# uARM.net
KiCad netlist of a schematic drawn in Altium Designer
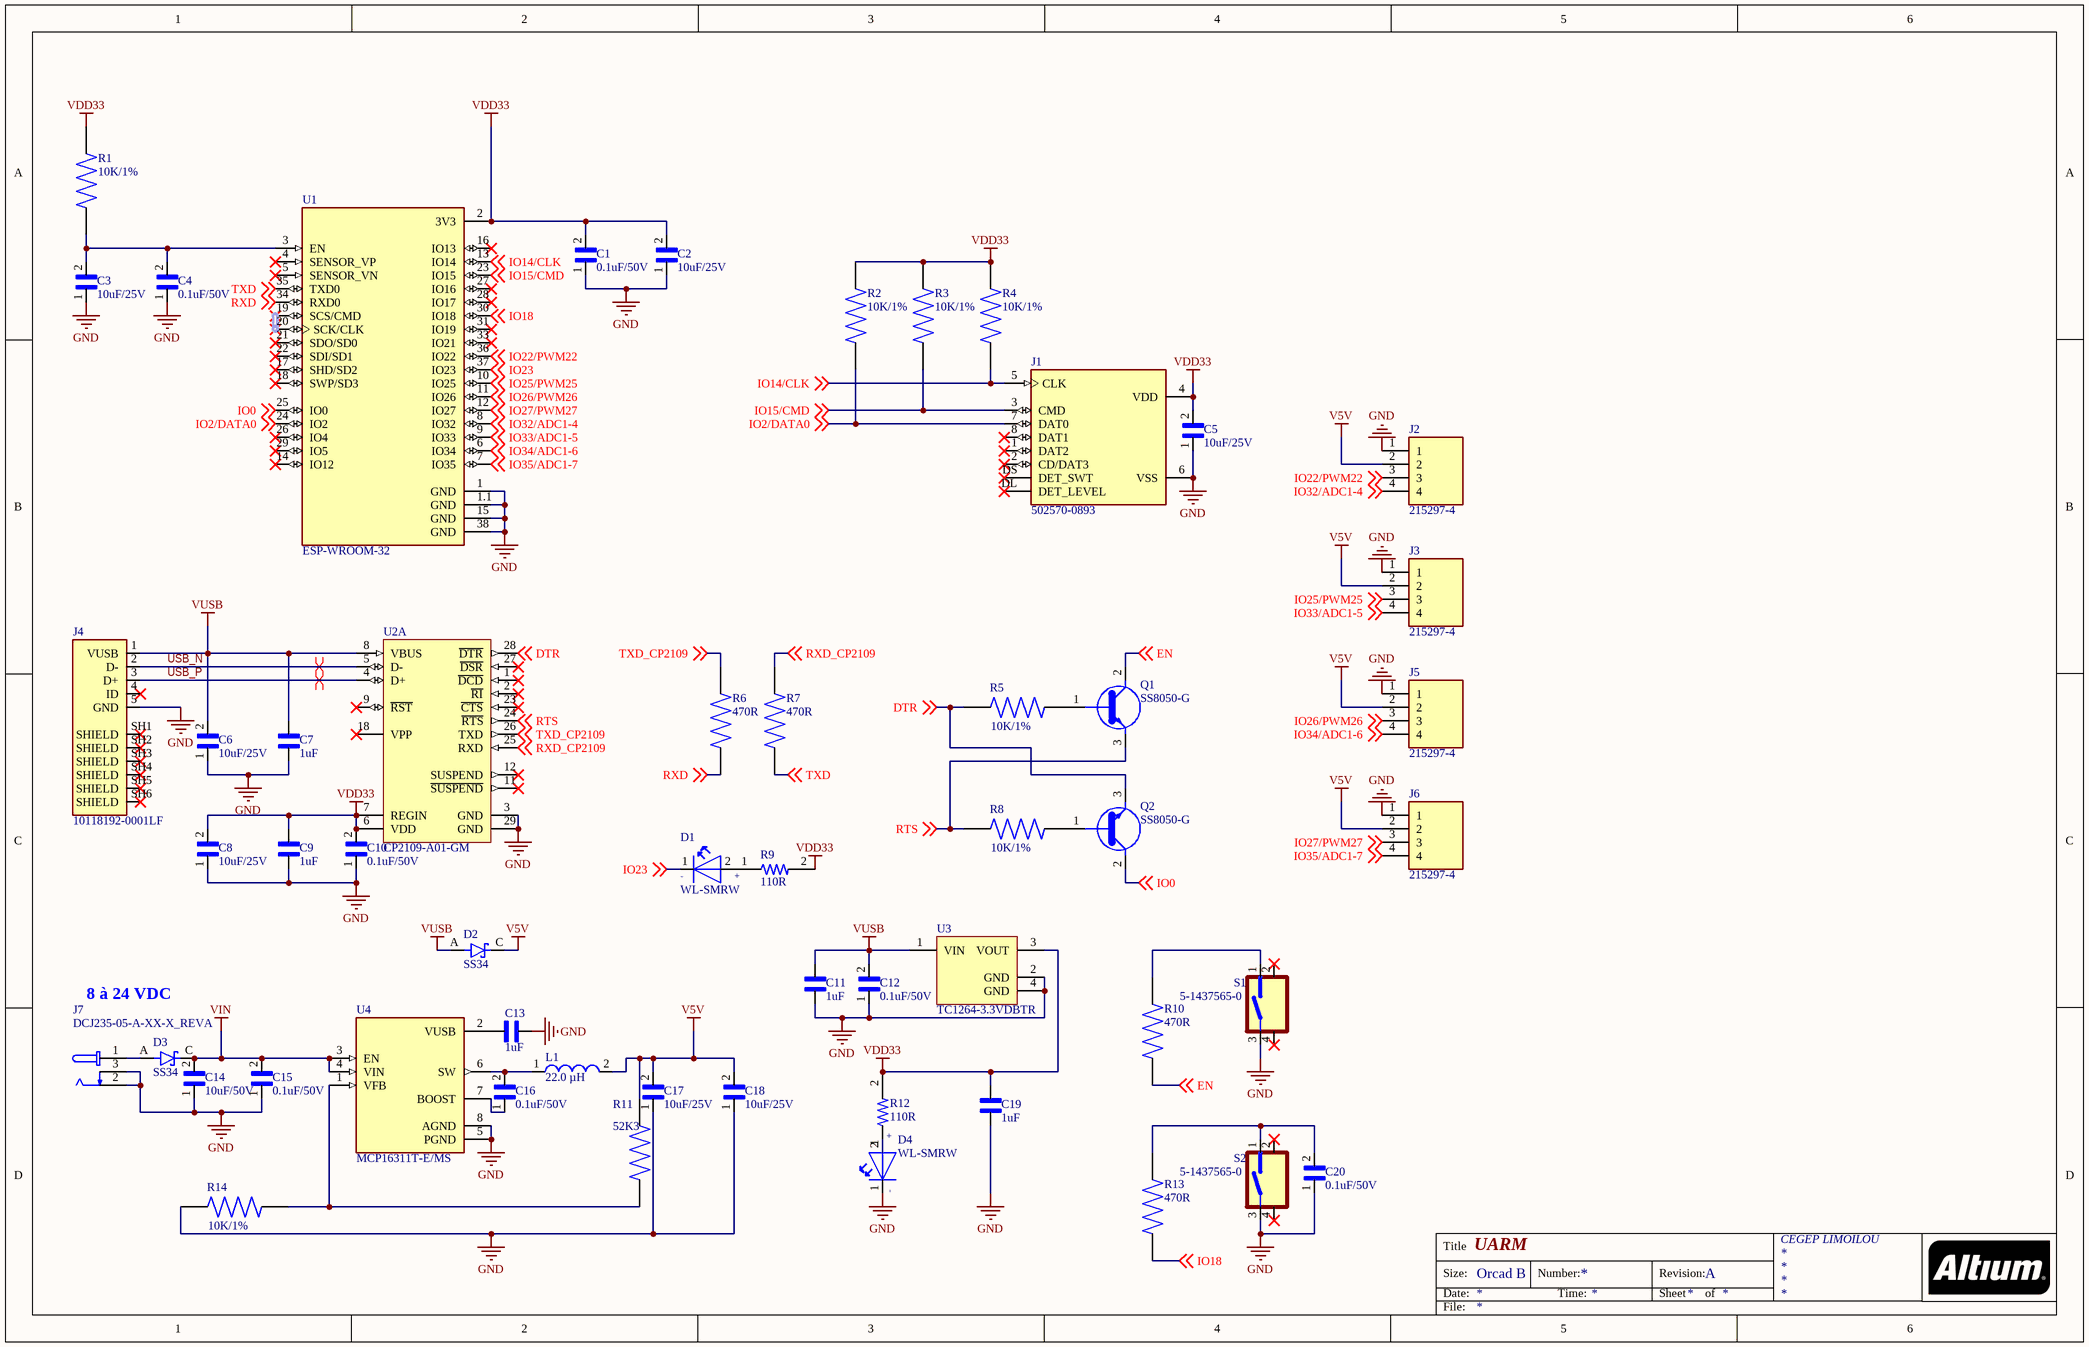
[diagram p0: uARM.SchDoc]

(export (version "E")
  (design (tool "Eeschema 10.0.6"))
  (components
    (comp (ref "C1")
      (value "0.1uF/50V")
      (footprint "08055C104KAT4A:CAPC2012X94N")
      (description ".1UF 50V 10% 0805")
      (fields (field (name "MF") "{'manufacturer': u'AVX'}") (field (name "MP") "08055C104KAT4A"))
      (libsource (lib "*") (part "08055C104KAT4A"))
    )
    (comp (ref "C2")
      (value "10uF/25V")
      (footprint "CL21A106KAYNNNE:CAPC2012X135N")
      (description "Cap Ceramic 10uF 25V X5R 10% SMD 0805 85Â°C Embossed T/R")
      (fields (field (name "MP") "CL21A106KAYNNNE") (field (name "MF") "{'manufacturer': u'Samsung'}"))
      (libsource (lib "*") (part "CL21A106KAYNNNE"))
    )
    (comp (ref "C3")
      (value "10uF/25V")
      (footprint "CL21A106KAYNNNE:CAPC2012X135N")
      (description "Cap Ceramic 10uF 25V X5R 10% SMD 0805 85Â°C Embossed T/R")
      (fields (field (name "MP") "CL21A106KAYNNNE") (field (name "MF") "{'manufacturer': u'Samsung'}"))
      (libsource (lib "*") (part "CL21A106KAYNNNE"))
    )
    (comp (ref "C4")
      (value "0.1uF/50V")
      (footprint "08055C104KAT4A:CAPC2012X94N")
      (description ".1UF 50V 10% 0805")
      (fields (field (name "MF") "{'manufacturer': u'AVX'}") (field (name "MP") "08055C104KAT4A"))
      (libsource (lib "*") (part "08055C104KAT4A"))
    )
    (comp (ref "C5")
      (value "10uF/25V")
      (footprint "CL21A106KAYNNNE:CAPC2012X135N")
      (description "Cap Ceramic 10uF 25V X5R 10% SMD 0805 85Â°C Embossed T/R")
      (fields (field (name "MP") "CL21A106KAYNNNE") (field (name "MF") "{'manufacturer': u'Samsung'}"))
      (libsource (lib "*") (part "CL21A106KAYNNNE"))
    )
    (comp (ref "C6")
      (value "10uF/25V")
      (footprint "CL21A106KAYNNNE:CAPC2012X135N")
      (description "Cap Ceramic 10uF 25V X5R 10% SMD 0805 85Â°C Embossed T/R")
      (fields (field (name "MP") "CL21A106KAYNNNE") (field (name "MF") "{'manufacturer': u'Samsung'}"))
      (libsource (lib "*") (part "CL21A106KAYNNNE"))
    )
    (comp (ref "C7")
      (value "1uF")
      (footprint "885012207022:WCAP-CSGP_885012207022")
      (fields
        (field (name "MF") "{'manufacturer': u'Wurth Electronics Inc'}")
        (field (name "MP") "885012207022")
      )
      (libsource (lib "") (part "885012207022_1"))
    )
    (comp (ref "C8")
      (value "10uF/25V")
      (footprint "CL21A106KAYNNNE:CAPC2012X135N")
      (description "Cap Ceramic 10uF 25V X5R 10% SMD 0805 85Â°C Embossed T/R")
      (fields (field (name "MP") "CL21A106KAYNNNE") (field (name "MF") "{'manufacturer': u'Samsung'}"))
      (libsource (lib "*") (part "CL21A106KAYNNNE"))
    )
    (comp (ref "C9")
      (value "1uF")
      (footprint "885012207022:WCAP-CSGP_885012207022")
      (fields
        (field (name "MF") "{'manufacturer': u'Wurth Electronics Inc'}")
        (field (name "MP") "885012207022")
      )
      (libsource (lib "") (part "885012207022_1"))
    )
    (comp (ref "C10")
      (value "0.1uF/50V")
      (footprint "08055C104KAT4A:CAPC2012X94N")
      (description ".1UF 50V 10% 0805")
      (fields (field (name "MF") "{'manufacturer': u'AVX'}") (field (name "MP") "08055C104KAT4A"))
      (libsource (lib "*") (part "08055C104KAT4A"))
    )
    (comp (ref "C11")
      (value "1uF")
      (footprint "885012207022:WCAP-CSGP_885012207022")
      (fields
        (field (name "MF") "{'manufacturer': u'Wurth Electronics Inc'}")
        (field (name "MP") "885012207022")
      )
      (libsource (lib "") (part "885012207022_1"))
    )
    (comp (ref "C12")
      (value "0.1uF/50V")
      (footprint "08055C104KAT4A:CAPC2012X94N")
      (description ".1UF 50V 10% 0805")
      (fields (field (name "MF") "{'manufacturer': u'AVX'}") (field (name "MP") "08055C104KAT4A"))
      (libsource (lib "*") (part "08055C104KAT4A"))
    )
    (comp (ref "C13")
      (value "1uF")
      (footprint "885012207022:WCAP-CSGP_885012207022")
      (fields
        (field (name "MF") "{'manufacturer': u'Wurth Electronics Inc'}")
        (field (name "MP") "885012207022")
      )
      (libsource (lib "*") (part "885012207022"))
    )
    (comp (ref "C14")
      (value "10uF/50V")
      (footprint "GRM21BR61H106KE43L:CAPC2012X145N")
      (description "SMD Capacitor X5R(EIA) with Capacitance: 10uF Tol. 10%. Rated Voltage: 50Vdc")
      (fields
        (field (name "MP") "GRM21BR61H106KE43L")
        (field (name "MF") "{'manufacturer': u'Murata Electronics'}")
      )
      (libsource (lib "*") (part "GRM21BR61H106KE43L"))
    )
    (comp (ref "C15")
      (value "0.1uF/50V")
      (footprint "08055C104KAT4A:CAPC2012X94N")
      (description ".1UF 50V 10% 0805")
      (fields (field (name "MF") "{'manufacturer': u'AVX'}") (field (name "MP") "08055C104KAT4A"))
      (libsource (lib "*") (part "08055C104KAT4A"))
    )
    (comp (ref "C16")
      (value "0.1uF/50V")
      (footprint "08055C104KAT4A:CAPC2012X94N")
      (description ".1UF 50V 10% 0805")
      (fields (field (name "MF") "{'manufacturer': u'AVX'}") (field (name "MP") "08055C104KAT4A"))
      (libsource (lib "*") (part "08055C104KAT4A"))
    )
    (comp (ref "C17")
      (value "10uF/25V")
      (footprint "CL21A106KAYNNNE:CAPC2012X135N")
      (description "Cap Ceramic 10uF 25V X5R 10% SMD 0805 85Â°C Embossed T/R")
      (fields (field (name "MP") "CL21A106KAYNNNE") (field (name "MF") "{'manufacturer': u'Samsung'}"))
      (libsource (lib "*") (part "CL21A106KAYNNNE"))
    )
    (comp (ref "C18")
      (value "10uF/25V")
      (footprint "CL21A106KAYNNNE:CAPC2012X135N")
      (description "Cap Ceramic 10uF 25V X5R 10% SMD 0805 85Â°C Embossed T/R")
      (fields (field (name "MP") "CL21A106KAYNNNE") (field (name "MF") "{'manufacturer': u'Samsung'}"))
      (libsource (lib "*") (part "CL21A106KAYNNNE"))
    )
    (comp (ref "C19")
      (value "1uF")
      (footprint "885012207022:WCAP-CSGP_885012207022")
      (fields
        (field (name "MF") "{'manufacturer': u'Wurth Electronics Inc'}")
        (field (name "MP") "885012207022")
      )
      (libsource (lib "") (part "885012207022_1"))
    )
    (comp (ref "C20")
      (value "0.1uF/50V")
      (footprint "08055C104KAT4A:CAPC2012X94N")
      (description ".1UF 50V 10% 0805")
      (fields (field (name "MF") "{'manufacturer': u'AVX'}") (field (name "MP") "08055C104KAT4A"))
      (libsource (lib "*") (part "08055C104KAT4A"))
    )
    (comp (ref "D1")
      (value "WL-SMRW")
      (footprint "156120GS75000:WL-SMRW-1206-RECT")
      (fields (field (name "MF") "{'manufacturer': u'Wurth Electronics'}"))
      (libsource (lib "*") (part "WL-SMRW"))
    )
    (comp (ref "D2")
      (value "SS34")
      (footprint "SS34:DIOM7959X265N")
      (description "Diode Schottky 40V 3A 2-Pin SMC T/R")
      (fields (field (name "MF") "{'manufacturer': u'ON Semiconductor'}"))
      (libsource (lib "*") (part "SS34"))
    )
    (comp (ref "D3")
      (value "SS34")
      (footprint "SS34:DIOM7959X265N")
      (description "Diode Schottky 40V 3A 2-Pin SMC T/R")
      (fields (field (name "MF") "{'manufacturer': u'ON Semiconductor'}"))
      (libsource (lib "*") (part "SS34"))
    )
    (comp (ref "D4")
      (value "WL-SMRW")
      (footprint "156120GS75000:WL-SMRW-1206-RECT")
      (fields (field (name "MF") "{'manufacturer': u'Wurth Electronics'}"))
      (libsource (lib "*") (part "WL-SMRW"))
    )
    (comp (ref "J1")
      (value "502570-0893")
      (footprint "502570-0893:MOLEX_502570-0893")
      (fields (field (name "MF") "{'manufacturer': u'Molex'}"))
      (libsource (lib "*") (part "502570-0893"))
    )
    (comp (ref "J2")
      (value "215297-4")
      (footprint "215297-4:TE_215297-4")
      (fields (field (name "MF") "{'manufacturer': u'TE Connectivity'}"))
      (libsource (lib "*") (part "215297-4"))
    )
    (comp (ref "J3")
      (value "215297-4")
      (footprint "215297-4:TE_215297-4")
      (fields (field (name "MF") "{'manufacturer': u'TE Connectivity'}"))
      (libsource (lib "*") (part "215297-4"))
    )
    (comp (ref "J4")
      (value "10118192-0001LF")
      (footprint "10118192-0001LF:AMPHENOL_10118192-0001LF")
      (description "Single Port 5 Contact Horizontal Right Angle Shielded Micro B USB 2.0 Connector")
      (fields (field (name "MF") "{'manufacturer': u'FCI'}"))
      (libsource (lib "*") (part "10118192-0001LF"))
    )
    (comp (ref "J5")
      (value "215297-4")
      (footprint "215297-4:TE_215297-4")
      (fields (field (name "MF") "{'manufacturer': u'TE Connectivity'}"))
      (libsource (lib "*") (part "215297-4"))
    )
    (comp (ref "J6")
      (value "215297-4")
      (footprint "215297-4:TE_215297-4")
      (fields (field (name "MF") "{'manufacturer': u'TE Connectivity'}"))
      (libsource (lib "*") (part "215297-4"))
    )
    (comp (ref "J7")
      (value "DCJ235-05-A-XX-X_REVA")
      (footprint "DCJ235-05-A-K1-A:GCT_DCJ235-05-A-XX-X_REVA")
      (description "DC Power Jack, Thru-Hole, Horizontal, with Locating Pegs, D2.35mm")
      (fields (field (name "MF") "{'manufacturer': u'Global Connector Technology'}"))
      (libsource (lib "*") (part "DCJ235-05-A-XX-X_REVA"))
    )
    (comp (ref "L1")
      (value "744773122")
      (footprint "WE-PD2-S")
      (description "SMD Power Inductor WE-PD2, L = 22.0 µH")
      (fields (field (name "INDUCTANCE") "22.0 µH"))
      (libsource (lib "Wurth_Electronics_744773122") (part "744773122"))
    )
    (comp (ref "Q1")
      (value "SS8050-G")
      (footprint "SS8050-G:MBTB-T-SOT23")
      (fields (field (name "MF") "{'manufacturer': u'Comchip Technology'}"))
      (libsource (lib "*") (part "SS8050-G"))
    )
    (comp (ref "Q2")
      (value "SS8050-G")
      (footprint "SS8050-G:MBTB-T-SOT23")
      (fields (field (name "MF") "{'manufacturer': u'Comchip Technology'}"))
      (libsource (lib "*") (part "SS8050-G"))
    )
    (comp (ref "R1")
      (value "10K/1%")
      (footprint "ESR10EZPF1002:RESC2012X65N")
      (description "RES SMD 10K OHM 1% 0.4W 0805")
      (fields (field (name "MF") "{'manufacturer': u'Rohm'}") (field (name "MP") "ESR10EZPF1002"))
      (libsource (lib "*") (part "ESR10EZPF1002"))
    )
    (comp (ref "R2")
      (value "10K/1%")
      (footprint "ESR10EZPF1002:RESC2012X65N")
      (description "RES SMD 10K OHM 1% 0.4W 0805")
      (fields (field (name "MF") "{'manufacturer': u'Rohm'}") (field (name "MP") "ESR10EZPF1002"))
      (libsource (lib "*") (part "ESR10EZPF1002"))
    )
    (comp (ref "R3")
      (value "10K/1%")
      (footprint "ESR10EZPF1002:RESC2012X65N")
      (description "RES SMD 10K OHM 1% 0.4W 0805")
      (fields (field (name "MF") "{'manufacturer': u'Rohm'}") (field (name "MP") "ESR10EZPF1002"))
      (libsource (lib "*") (part "ESR10EZPF1002"))
    )
    (comp (ref "R4")
      (value "10K/1%")
      (footprint "ESR10EZPF1002:RESC2012X65N")
      (description "RES SMD 10K OHM 1% 0.4W 0805")
      (fields (field (name "MF") "{'manufacturer': u'Rohm'}") (field (name "MP") "ESR10EZPF1002"))
      (libsource (lib "*") (part "ESR10EZPF1002"))
    )
    (comp (ref "R5")
      (value "10K/1%")
      (footprint "ESR10EZPF1002:RESC2012X65N")
      (description "RES SMD 10K OHM 1% 0.4W 0805")
      (fields (field (name "MF") "{'manufacturer': u'Rohm'}") (field (name "MP") "ESR10EZPF1002"))
      (libsource (lib "*") (part "ESR10EZPF1002"))
    )
    (comp (ref "R6")
      (value "470R")
      (footprint "ERJ-PB6B4700V:RESC2012X70N")
      (fields (field (name "MP") "ERJ-PB6B4700V") (field (name "MF") "{'manufacturer': u'Panasonic'}"))
      (libsource (lib "*") (part "ERJ-PB6B4700V"))
    )
    (comp (ref "R7")
      (value "470R")
      (footprint "ERJ-PB6B4700V:RESC2012X70N")
      (fields (field (name "MP") "ERJ-PB6B4700V") (field (name "MF") "{'manufacturer': u'Panasonic'}"))
      (libsource (lib "*") (part "ERJ-PB6B4700V"))
    )
    (comp (ref "R8")
      (value "10K/1%")
      (footprint "ESR10EZPF1002:RESC2012X65N")
      (description "RES SMD 10K OHM 1% 0.4W 0805")
      (fields (field (name "MF") "{'manufacturer': u'Rohm'}") (field (name "MP") "ESR10EZPF1002"))
      (libsource (lib "*") (part "ESR10EZPF1002"))
    )
    (comp (ref "R9")
      (value "110R")
      (footprint "RK73H2ATTD1100F:RESCAV127P508X200X70-8N")
      (description "Res Thick Film 0805 110 Ohm 1% 1/8W ?100ppm/C Molded SMD SMD Punched Paper T/R")
      (fields (field (name "MP") "RK73H2ATTD1100F") (field (name "MF") "{'manufacturer': u'KOA Speer'}"))
      (libsource (lib "*") (part "RK73H2ATTD1100F"))
    )
    (comp (ref "R10")
      (value "470R")
      (footprint "ERJ-PB6B4700V:RESC2012X70N")
      (fields (field (name "MP") "ERJ-PB6B4700V") (field (name "MF") "{'manufacturer': u'Panasonic'}"))
      (libsource (lib "*") (part "ERJ-PB6B4700V"))
    )
    (comp (ref "R11")
      (value "52K3")
      (footprint "ERJ-1GEF5232C:RESC0603X26N")
      (description "Res Thick Film 0201 52.3K Ohm 1% 0.05W(1/20W) Â±200ppm/C SMD T/R")
      (fields (field (name "MP") "ERJ-1GEF5232C") (field (name "MF") "{'manufacturer': u'Panasonic'}"))
      (libsource (lib "*") (part "ERJ-1GEF5232C"))
    )
    (comp (ref "R12")
      (value "110R")
      (footprint "RK73H2ATTD1100F:RESCAV127P508X200X70-8N")
      (description "Res Thick Film 0805 110 Ohm 1% 1/8W ?100ppm/C Molded SMD SMD Punched Paper T/R")
      (fields (field (name "MP") "RK73H2ATTD1100F") (field (name "MF") "{'manufacturer': u'KOA Speer'}"))
      (libsource (lib "*") (part "RK73H2ATTD1100F"))
    )
    (comp (ref "R13")
      (value "470R")
      (footprint "ERJ-PB6B4700V:RESC2012X70N")
      (fields (field (name "MP") "ERJ-PB6B4700V") (field (name "MF") "{'manufacturer': u'Panasonic'}"))
      (libsource (lib "*") (part "ERJ-PB6B4700V"))
    )
    (comp (ref "R14")
      (value "10K/1%")
      (footprint "ESR10EZPF1002:RESC2012X65N")
      (description "RES SMD 10K OHM 1% 0.4W 0805")
      (fields (field (name "MF") "{'manufacturer': u'Rohm'}") (field (name "MP") "ESR10EZPF1002"))
      (libsource (lib "*") (part "ESR10EZPF1002"))
    )
    (comp (ref "S1")
      (value "5-1437565-0")
      (footprint "FSM6JSMATR:SW_5-1437565-0")
      (description "Switch Tactile OFF (ON) Round Button Gull Wing 0.05A 12VDC 1.57N SMD T/R")
      (fields (field (name "MF") "{'manufacturer': u'TE Connectivity'}"))
      (libsource (lib "*") (part "5-1437565-0"))
    )
    (comp (ref "S2")
      (value "5-1437565-0")
      (footprint "FSM6JSMATR:SW_5-1437565-0")
      (description "Switch Tactile OFF (ON) Round Button Gull Wing 0.05A 12VDC 1.57N SMD T/R")
      (fields (field (name "MF") "{'manufacturer': u'TE Connectivity'}"))
      (libsource (lib "*") (part "5-1437565-0"))
    )
    (comp (ref "U1")
      (value "ESP-WROOM-32")
      (footprint "ESP-WROOM-32:MODULE_ESP-WROOM-32")
      (description "Module: combo; GPIO, I2C x2, I2S x2, SDIO, SPI x3, UART x3; 19.5dBm")
      (fields (field (name "MF") "{'manufacturer': u'Espressif Systems'}"))
      (libsource (lib "*") (part "ESP-WROOM-32"))
    )
    (comp (ref "U2")
      (value "CP2109-A01-GM")
      (footprint "SLAB-QFN-28-3125x3125TP_L")
      (description "Single-Chip USB to UART Bridge, 1024 Bytes EEPROM, -40 to 85 degC, 28-pin QFN, Tube")
      (fields (field (name "MANUFACTURER") "Silicon Labs"))
      (libsource (lib "Silicon_Labs_CP2109_A01_GM") (part "CP2109-A01-GM"))
    )
    (comp (ref "U3")
      (value "TC1264-3.3VDBTR")
      (footprint "SOT-223-DB3_L")
      (description "800 mA Fixed-Output CMOS LDO with Shutdown, 3-Pin SOT-223, Extended Temperature, Tape and Reel")
      (libsource (lib "Microchip_TC1264_3_3VDBTR") (part "TC1264-3.3VDBTR"))
    )
    (comp (ref "U4")
      (value "MCP16311T-E/MS")
      (footprint "MCP16311T-E_MS:SOP65P490X110-8N")
      (fields (field (name "MF") "{'manufacturer': u'Microchip Technology'}"))
      (libsource (lib "*") (part "MCP16311T-E/MS"))
    )
  )
  (nets
    (net (code "1") (name "/USB_N") (class "Default")
      (node (ref "J4") (pin "2") (pinfunction "D-_2") (pintype "passive"))
      (node (ref "U2") (pin "5") (pinfunction "D-_5") (pintype "bidirectional"))
    )
    (net (code "2") (name "/USB_P") (class "Default")
      (node (ref "J4") (pin "3") (pinfunction "D+_3") (pintype "passive"))
      (node (ref "U2") (pin "4") (pinfunction "D+_4") (pintype "bidirectional"))
    )
    (net (code "3") (name "DTR") (class "Default")
      (node (ref "Q2") (pin "3") (pinfunction "C_3") (pintype "bidirectional"))
      (node (ref "R5") (pin "1") (pinfunction "1_1") (pintype "passive"))
      (node (ref "U2") (pin "28") (pinfunction "~{DTR}_28") (pintype "output"))
    )
    (net (code "4") (name "EN") (class "Default")
      (node (ref "Q1") (pin "2") (pinfunction "E_2") (pintype "bidirectional"))
      (node (ref "R10") (pin "1") (pinfunction "1_1") (pintype "passive"))
    )
    (net (code "5") (name "GND") (class "Default")
      (node (ref "C1") (pin "1") (pinfunction "1_1") (pintype "passive"))
      (node (ref "C10") (pin "1") (pinfunction "1_1") (pintype "passive"))
      (node (ref "C11") (pin "2") (pinfunction "2_2") (pintype "passive"))
      (node (ref "C12") (pin "1") (pinfunction "1_1") (pintype "passive"))
      (node (ref "C13") (pin "1") (pinfunction "1_1") (pintype "passive"))
      (node (ref "C14") (pin "1") (pinfunction "1_1") (pintype "passive"))
      (node (ref "C15") (pin "1") (pinfunction "1_1") (pintype "passive"))
      (node (ref "C17") (pin "1") (pinfunction "1_1") (pintype "passive"))
      (node (ref "C18") (pin "1") (pinfunction "1_1") (pintype "passive"))
      (node (ref "C19") (pin "2") (pinfunction "2_2") (pintype "passive"))
      (node (ref "C2") (pin "1") (pinfunction "1_1") (pintype "passive"))
      (node (ref "C20") (pin "1") (pinfunction "1_1") (pintype "passive"))
      (node (ref "C3") (pin "1") (pinfunction "1_1") (pintype "passive"))
      (node (ref "C4") (pin "1") (pinfunction "1_1") (pintype "passive"))
      (node (ref "C5") (pin "1") (pinfunction "1_1") (pintype "passive"))
      (node (ref "C6") (pin "1") (pinfunction "1_1") (pintype "passive"))
      (node (ref "C7") (pin "2") (pinfunction "2_2") (pintype "passive"))
      (node (ref "C8") (pin "1") (pinfunction "1_1") (pintype "passive"))
      (node (ref "C9") (pin "2") (pinfunction "2_2") (pintype "passive"))
      (node (ref "D4") (pin "1") (pinfunction "NEG_1") (pintype "bidirectional"))
      (node (ref "J1") (pin "6") (pinfunction "VSS_6") (pintype "power_in"))
      (node (ref "J2") (pin "1") (pinfunction "1_1") (pintype "passive"))
      (node (ref "J3") (pin "1") (pinfunction "1_1") (pintype "passive"))
      (node (ref "J4") (pin "5") (pinfunction "GND_5") (pintype "passive"))
      (node (ref "J5") (pin "1") (pinfunction "1_1") (pintype "passive"))
      (node (ref "J6") (pin "1") (pinfunction "1_1") (pintype "passive"))
      (node (ref "J7") (pin "2") (pinfunction "2_2") (pintype "passive"))
      (node (ref "J7") (pin "3") (pinfunction "3_3") (pintype "passive"))
      (node (ref "R14") (pin "1") (pinfunction "1_1") (pintype "passive"))
      (node (ref "S1") (pin "3") (pinfunction "1_3") (pintype "passive"))
      (node (ref "S2") (pin "3") (pinfunction "1_3") (pintype "passive"))
      (node (ref "U1") (pin "1") (pinfunction "GND_1") (pintype "power_in"))
      (node (ref "U1") (pin "1.1") (pinfunction "GND_1.1") (pintype "power_in"))
      (node (ref "U1") (pin "15") (pinfunction "GND_15") (pintype "power_in"))
      (node (ref "U1") (pin "38") (pinfunction "GND_38") (pintype "power_in"))
      (node (ref "U2") (pin "29") (pinfunction "GND_29") (pintype "power_in"))
      (node (ref "U2") (pin "3") (pinfunction "GND_3") (pintype "power_in"))
      (node (ref "U3") (pin "2") (pinfunction "GND_2") (pintype "power_in"))
      (node (ref "U3") (pin "4") (pinfunction "GND_4") (pintype "power_in"))
      (node (ref "U4") (pin "5") (pinfunction "PGND_5") (pintype "power_in"))
      (node (ref "U4") (pin "8") (pinfunction "AGND_8") (pintype "power_in"))
    )
    (net (code "6") (name "IO0") (class "Default")
      (node (ref "Q2") (pin "2") (pinfunction "E_2") (pintype "bidirectional"))
      (node (ref "U1") (pin "25") (pinfunction "IO0_25") (pintype "bidirectional"))
    )
    (net (code "7") (name "IO2{slash}DATA0") (class "Default")
      (node (ref "J1") (pin "7") (pinfunction "DAT0_7") (pintype "bidirectional"))
      (node (ref "R2") (pin "1") (pinfunction "1_1") (pintype "passive"))
      (node (ref "U1") (pin "24") (pinfunction "IO2_24") (pintype "bidirectional"))
    )
    (net (code "8") (name "IO14{slash}CLK") (class "Default")
      (node (ref "J1") (pin "5") (pinfunction "CLK_5") (pintype "input"))
      (node (ref "R4") (pin "1") (pinfunction "1_1") (pintype "passive"))
      (node (ref "U1") (pin "13") (pinfunction "IO14_13") (pintype "bidirectional"))
    )
    (net (code "9") (name "IO15{slash}CMD") (class "Default")
      (node (ref "J1") (pin "3") (pinfunction "CMD_3") (pintype "bidirectional"))
      (node (ref "R3") (pin "1") (pinfunction "1_1") (pintype "passive"))
      (node (ref "U1") (pin "23") (pinfunction "IO15_23") (pintype "bidirectional"))
    )
    (net (code "10") (name "IO18") (class "Default")
      (node (ref "R13") (pin "1") (pinfunction "1_1") (pintype "passive"))
      (node (ref "U1") (pin "30") (pinfunction "IO18_30") (pintype "bidirectional"))
    )
    (net (code "11") (name "IO22{slash}PWM22") (class "Default")
      (node (ref "J2") (pin "3") (pinfunction "3_3") (pintype "passive"))
      (node (ref "U1") (pin "36") (pinfunction "IO22_36") (pintype "bidirectional"))
    )
    (net (code "12") (name "IO23") (class "Default")
      (node (ref "D1") (pin "1") (pinfunction "NEG_1") (pintype "bidirectional"))
      (node (ref "U1") (pin "37") (pinfunction "IO23_37") (pintype "bidirectional"))
    )
    (net (code "13") (name "IO25{slash}PWM25") (class "Default")
      (node (ref "J3") (pin "3") (pinfunction "3_3") (pintype "passive"))
      (node (ref "U1") (pin "10") (pinfunction "IO25_10") (pintype "bidirectional"))
    )
    (net (code "14") (name "IO26{slash}PWM26") (class "Default")
      (node (ref "J5") (pin "3") (pinfunction "3_3") (pintype "passive"))
      (node (ref "U1") (pin "11") (pinfunction "IO26_11") (pintype "bidirectional"))
    )
    (net (code "15") (name "IO27{slash}PWM27") (class "Default")
      (node (ref "J6") (pin "3") (pinfunction "3_3") (pintype "passive"))
      (node (ref "U1") (pin "12") (pinfunction "IO27_12") (pintype "bidirectional"))
    )
    (net (code "16") (name "IO32{slash}ADC1-4") (class "Default")
      (node (ref "J2") (pin "4") (pinfunction "4_4") (pintype "passive"))
      (node (ref "U1") (pin "8") (pinfunction "IO32_8") (pintype "bidirectional"))
    )
    (net (code "17") (name "IO33{slash}ADC1-5") (class "Default")
      (node (ref "J3") (pin "4") (pinfunction "4_4") (pintype "passive"))
      (node (ref "U1") (pin "9") (pinfunction "IO33_9") (pintype "bidirectional"))
    )
    (net (code "18") (name "IO34{slash}ADC1-6") (class "Default")
      (node (ref "J5") (pin "4") (pinfunction "4_4") (pintype "passive"))
      (node (ref "U1") (pin "6") (pinfunction "IO34_6") (pintype "bidirectional"))
    )
    (net (code "19") (name "IO35{slash}ADC1-7") (class "Default")
      (node (ref "J6") (pin "4") (pinfunction "4_4") (pintype "passive"))
      (node (ref "U1") (pin "7") (pinfunction "IO35_7") (pintype "bidirectional"))
    )
    (net (code "20") (name "Net-(C20-Pad2)") (class "Default")
      (node (ref "C20") (pin "2") (pinfunction "2_2") (pintype "passive"))
      (node (ref "R13") (pin "2") (pinfunction "2_2") (pintype "passive"))
      (node (ref "S2") (pin "1") (pinfunction "2_1") (pintype "passive"))
    )
    (net (code "21") (name "Net-(D1-POS)") (class "Default")
      (node (ref "D1") (pin "2") (pinfunction "POS_2") (pintype "bidirectional"))
      (node (ref "R9") (pin "1") (pinfunction "1_1") (pintype "passive"))
    )
    (net (code "22") (name "Net-(D3-PadA)") (class "Default")
      (node (ref "D3") (pin "A") (pinfunction "A_A") (pintype "passive"))
      (node (ref "J7") (pin "1") (pinfunction "1_1") (pintype "passive"))
    )
    (net (code "23") (name "Net-(D4-POS)") (class "Default")
      (node (ref "D4") (pin "2") (pinfunction "POS_2") (pintype "bidirectional"))
      (node (ref "R12") (pin "1") (pinfunction "1_1") (pintype "passive"))
    )
    (net (code "24") (name "Net-(Q1-B)") (class "Default")
      (node (ref "Q1") (pin "1") (pinfunction "B_1") (pintype "bidirectional"))
      (node (ref "R5") (pin "2") (pinfunction "2_2") (pintype "passive"))
    )
    (net (code "25") (name "Net-(Q2-B)") (class "Default")
      (node (ref "Q2") (pin "1") (pinfunction "B_1") (pintype "bidirectional"))
      (node (ref "R8") (pin "2") (pinfunction "2_2") (pintype "passive"))
    )
    (net (code "26") (name "Net-(R10-Pad2)") (class "Default")
      (node (ref "R10") (pin "2") (pinfunction "2_2") (pintype "passive"))
      (node (ref "S1") (pin "1") (pinfunction "2_1") (pintype "passive"))
    )
    (net (code "27") (name "Net-(U1-EN)") (class "Default")
      (node (ref "C3") (pin "2") (pinfunction "2_2") (pintype "passive"))
      (node (ref "C4") (pin "2") (pinfunction "2_2") (pintype "passive"))
      (node (ref "R1") (pin "1") (pinfunction "1_1") (pintype "passive"))
      (node (ref "U1") (pin "3") (pinfunction "EN_3") (pintype "input"))
    )
    (net (code "28") (name "Net-(U4-BOOST)") (class "Default")
      (node (ref "C16") (pin "1") (pinfunction "1_1") (pintype "passive"))
      (node (ref "U4") (pin "7") (pinfunction "BOOST_7") (pintype "passive"))
    )
    (net (code "29") (name "Net-(U4-SW)") (class "Default")
      (node (ref "C16") (pin "2") (pinfunction "2_2") (pintype "passive"))
      (node (ref "L1") (pin "1") (pinfunction "1_1") (pintype "passive"))
      (node (ref "U4") (pin "6") (pinfunction "SW_6") (pintype "output"))
    )
    (net (code "30") (name "Net-(U4-VFB)") (class "Default")
      (node (ref "R11") (pin "1") (pinfunction "1_1") (pintype "passive"))
      (node (ref "R14") (pin "2") (pinfunction "2_2") (pintype "passive"))
      (node (ref "U4") (pin "1") (pinfunction "VFB_1") (pintype "input"))
    )
    (net (code "31") (name "Net-(U4-VUSB)") (class "Default")
      (node (ref "C13") (pin "2") (pinfunction "2_2") (pintype "passive"))
      (node (ref "U4") (pin "2") (pinfunction "VUSB_2") (pintype "power_in"))
    )
    (net (code "32") (name "RTS") (class "Default")
      (node (ref "Q1") (pin "3") (pinfunction "C_3") (pintype "bidirectional"))
      (node (ref "R8") (pin "1") (pinfunction "1_1") (pintype "passive"))
      (node (ref "U2") (pin "24") (pinfunction "~{RTS}_24") (pintype "output"))
    )
    (net (code "33") (name "RXD") (class "Default")
      (node (ref "R6") (pin "1") (pinfunction "1_1") (pintype "passive"))
      (node (ref "U1") (pin "34") (pinfunction "RXD0_34") (pintype "bidirectional"))
    )
    (net (code "34") (name "RXD_CP2109") (class "Default")
      (node (ref "R7") (pin "2") (pinfunction "2_2") (pintype "passive"))
      (node (ref "U2") (pin "25") (pinfunction "RXD_25") (pintype "input"))
    )
    (net (code "35") (name "TXD") (class "Default")
      (node (ref "R7") (pin "1") (pinfunction "1_1") (pintype "passive"))
      (node (ref "U1") (pin "35") (pinfunction "TXD0_35") (pintype "bidirectional"))
    )
    (net (code "36") (name "TXD_CP2109") (class "Default")
      (node (ref "R6") (pin "2") (pinfunction "2_2") (pintype "passive"))
      (node (ref "U2") (pin "26") (pinfunction "TXD_26") (pintype "output"))
    )
    (net (code "37") (name "V5V") (class "Default")
      (node (ref "C17") (pin "2") (pinfunction "2_2") (pintype "passive"))
      (node (ref "C18") (pin "2") (pinfunction "2_2") (pintype "passive"))
      (node (ref "D2") (pin "C") (pinfunction "K_C") (pintype "passive"))
      (node (ref "J2") (pin "2") (pinfunction "2_2") (pintype "passive"))
      (node (ref "J3") (pin "2") (pinfunction "2_2") (pintype "passive"))
      (node (ref "J5") (pin "2") (pinfunction "2_2") (pintype "passive"))
      (node (ref "J6") (pin "2") (pinfunction "2_2") (pintype "passive"))
      (node (ref "L1") (pin "2") (pinfunction "2_2") (pintype "passive"))
      (node (ref "R11") (pin "2") (pinfunction "2_2") (pintype "passive"))
    )
    (net (code "38") (name "VDD33") (class "Default")
      (node (ref "C1") (pin "2") (pinfunction "2_2") (pintype "passive"))
      (node (ref "C10") (pin "2") (pinfunction "2_2") (pintype "passive"))
      (node (ref "C19") (pin "1") (pinfunction "1_1") (pintype "passive"))
      (node (ref "C2") (pin "2") (pinfunction "2_2") (pintype "passive"))
      (node (ref "C5") (pin "2") (pinfunction "2_2") (pintype "passive"))
      (node (ref "C8") (pin "2") (pinfunction "2_2") (pintype "passive"))
      (node (ref "C9") (pin "1") (pinfunction "1_1") (pintype "passive"))
      (node (ref "J1") (pin "4") (pinfunction "VDD_4") (pintype "power_in"))
      (node (ref "R1") (pin "2") (pinfunction "2_2") (pintype "passive"))
      (node (ref "R12") (pin "2") (pinfunction "2_2") (pintype "passive"))
      (node (ref "R2") (pin "2") (pinfunction "2_2") (pintype "passive"))
      (node (ref "R3") (pin "2") (pinfunction "2_2") (pintype "passive"))
      (node (ref "R4") (pin "2") (pinfunction "2_2") (pintype "passive"))
      (node (ref "R9") (pin "2") (pinfunction "2_2") (pintype "passive"))
      (node (ref "U1") (pin "2") (pinfunction "3V3_2") (pintype "power_in"))
      (node (ref "U2") (pin "6") (pinfunction "VDD_6") (pintype "power_in"))
      (node (ref "U2") (pin "7") (pinfunction "REGIN_7") (pintype "power_in"))
      (node (ref "U3") (pin "3") (pinfunction "VOUT_3") (pintype "power_in"))
    )
    (net (code "39") (name "VIN") (class "Default")
      (node (ref "C14") (pin "2") (pinfunction "2_2") (pintype "passive"))
      (node (ref "C15") (pin "2") (pinfunction "2_2") (pintype "passive"))
      (node (ref "D3") (pin "C") (pinfunction "K_C") (pintype "passive"))
      (node (ref "U4") (pin "3") (pinfunction "EN_3") (pintype "input"))
      (node (ref "U4") (pin "4") (pinfunction "VIN_4") (pintype "input"))
    )
    (net (code "40") (name "VUSB") (class "Default")
      (node (ref "C11") (pin "1") (pinfunction "1_1") (pintype "passive"))
      (node (ref "C12") (pin "2") (pinfunction "2_2") (pintype "passive"))
      (node (ref "C6") (pin "2") (pinfunction "2_2") (pintype "passive"))
      (node (ref "C7") (pin "1") (pinfunction "1_1") (pintype "passive"))
      (node (ref "D2") (pin "A") (pinfunction "A_A") (pintype "passive"))
      (node (ref "J4") (pin "1") (pinfunction "VUSB_1") (pintype "passive"))
      (node (ref "U2") (pin "8") (pinfunction "VBUS_8") (pintype "input"))
      (node (ref "U3") (pin "1") (pinfunction "VIN_1") (pintype "power_in"))
    )
    (net (code "41") (name "unconnected-(J1-CD{slash}DAT3-Pad2)") (class "Default")
      (node (ref "J1") (pin "2") (pinfunction "CD/DAT3_2") (pintype "bidirectional+no_connect"))
    )
    (net (code "42") (name "unconnected-(J1-DAT1-Pad8)") (class "Default")
      (node (ref "J1") (pin "8") (pinfunction "DAT1_8") (pintype "bidirectional+no_connect"))
    )
    (net (code "43") (name "unconnected-(J1-DAT2-Pad1)") (class "Default")
      (node (ref "J1") (pin "1") (pinfunction "DAT2_1") (pintype "bidirectional+no_connect"))
    )
    (net (code "44") (name "unconnected-(J1-DET_LEVEL-PadDL)") (class "Default")
      (node (ref "J1") (pin "DL") (pinfunction "DET_LEVEL_DL") (pintype "passive+no_connect"))
    )
    (net (code "45") (name "unconnected-(J1-DET_SWT-PadDS)") (class "Default")
      (node (ref "J1") (pin "DS") (pinfunction "DET_SWT_DS") (pintype "passive+no_connect"))
    )
    (net (code "46") (name "unconnected-(J4-ID-Pad4)") (class "Default")
      (node (ref "J4") (pin "4") (pinfunction "ID_4") (pintype "passive+no_connect"))
    )
    (net (code "47") (name "unconnected-(J4-SHIELD-PadSH1)") (class "Default")
      (node (ref "J4") (pin "SH1") (pinfunction "SHIELD_SH1") (pintype "passive+no_connect"))
    )
    (net (code "48") (name "unconnected-(J4-SHIELD-PadSH2)") (class "Default")
      (node (ref "J4") (pin "SH2") (pinfunction "SHIELD_SH2") (pintype "passive+no_connect"))
    )
    (net (code "49") (name "unconnected-(J4-SHIELD-PadSH3)") (class "Default")
      (node (ref "J4") (pin "SH3") (pinfunction "SHIELD_SH3") (pintype "passive+no_connect"))
    )
    (net (code "50") (name "unconnected-(J4-SHIELD-PadSH4)") (class "Default")
      (node (ref "J4") (pin "SH4") (pinfunction "SHIELD_SH4") (pintype "passive+no_connect"))
    )
    (net (code "51") (name "unconnected-(J4-SHIELD-PadSH5)") (class "Default")
      (node (ref "J4") (pin "SH5") (pinfunction "SHIELD_SH5") (pintype "passive+no_connect"))
    )
    (net (code "52") (name "unconnected-(J4-SHIELD-PadSH6)") (class "Default")
      (node (ref "J4") (pin "SH6") (pinfunction "SHIELD_SH6") (pintype "passive+no_connect"))
    )
    (net (code "53") (name "unconnected-(S1-1-Pad4)") (class "Default")
      (node (ref "S1") (pin "4") (pinfunction "1_4") (pintype "passive+no_connect"))
    )
    (net (code "54") (name "unconnected-(S1-Pad2)") (class "Default")
      (node (ref "S1") (pin "2") (pinfunction "2_2") (pintype "passive+no_connect"))
    )
    (net (code "55") (name "unconnected-(S2-1-Pad4)") (class "Default")
      (node (ref "S2") (pin "4") (pinfunction "1_4") (pintype "passive+no_connect"))
    )
    (net (code "56") (name "unconnected-(S2-Pad2)") (class "Default")
      (node (ref "S2") (pin "2") (pinfunction "2_2") (pintype "passive+no_connect"))
    )
    (net (code "57") (name "unconnected-(U1-IO4-Pad26)") (class "Default")
      (node (ref "U1") (pin "26") (pinfunction "IO4_26") (pintype "bidirectional+no_connect"))
    )
    (net (code "58") (name "unconnected-(U1-IO5-Pad29)") (class "Default")
      (node (ref "U1") (pin "29") (pinfunction "IO5_29") (pintype "bidirectional+no_connect"))
    )
    (net (code "59") (name "unconnected-(U1-IO12-Pad14)") (class "Default")
      (node (ref "U1") (pin "14") (pinfunction "IO12_14") (pintype "bidirectional+no_connect"))
    )
    (net (code "60") (name "unconnected-(U1-IO13-Pad16)") (class "Default")
      (node (ref "U1") (pin "16") (pinfunction "IO13_16") (pintype "bidirectional+no_connect"))
    )
    (net (code "61") (name "unconnected-(U1-IO16-Pad27)") (class "Default")
      (node (ref "U1") (pin "27") (pinfunction "IO16_27") (pintype "bidirectional+no_connect"))
    )
    (net (code "62") (name "unconnected-(U1-IO17-Pad28)") (class "Default")
      (node (ref "U1") (pin "28") (pinfunction "IO17_28") (pintype "bidirectional+no_connect"))
    )
    (net (code "63") (name "unconnected-(U1-IO19-Pad31)") (class "Default")
      (node (ref "U1") (pin "31") (pinfunction "IO19_31") (pintype "bidirectional+no_connect"))
    )
    (net (code "64") (name "unconnected-(U1-IO21-Pad33)") (class "Default")
      (node (ref "U1") (pin "33") (pinfunction "IO21_33") (pintype "bidirectional+no_connect"))
    )
    (net (code "65") (name "unconnected-(U1-SCK{slash}CLK-Pad20)") (class "Default")
      (node (ref "U1") (pin "19") (pinfunction "SCS/CMD_19") (pintype "bidirectional"))
      (node (ref "U1") (pin "20") (pinfunction "SCK/CLK_20") (pintype "bidirectional"))
    )
    (net (code "66") (name "unconnected-(U1-SDI{slash}SD1-Pad22)") (class "Default")
      (node (ref "U1") (pin "22") (pinfunction "SDI/SD1_22") (pintype "bidirectional+no_connect"))
    )
    (net (code "67") (name "unconnected-(U1-SDO{slash}SD0-Pad21)") (class "Default")
      (node (ref "U1") (pin "21") (pinfunction "SDO/SD0_21") (pintype "bidirectional+no_connect"))
    )
    (net (code "68") (name "unconnected-(U1-SENSOR_VN-Pad5)") (class "Default")
      (node (ref "U1") (pin "5") (pinfunction "SENSOR_VN_5") (pintype "input+no_connect"))
    )
    (net (code "69") (name "unconnected-(U1-SENSOR_VP-Pad4)") (class "Default")
      (node (ref "U1") (pin "4") (pinfunction "SENSOR_VP_4") (pintype "input+no_connect"))
    )
    (net (code "70") (name "unconnected-(U1-SHD{slash}SD2-Pad17)") (class "Default")
      (node (ref "U1") (pin "17") (pinfunction "SHD/SD2_17") (pintype "bidirectional+no_connect"))
    )
    (net (code "71") (name "unconnected-(U1-SWP{slash}SD3-Pad18)") (class "Default")
      (node (ref "U1") (pin "18") (pinfunction "SWP/SD3_18") (pintype "bidirectional+no_connect"))
    )
    (net (code "72") (name "unconnected-(U2A-SUSPEND-Pad12)") (class "Default")
      (node (ref "U2") (pin "12") (pinfunction "SUSPEND_12") (pintype "output+no_connect"))
    )
    (net (code "73") (name "unconnected-(U2A-VPP-Pad18)") (class "Default")
      (node (ref "U2") (pin "18") (pinfunction "VPP_18") (pintype "passive+no_connect"))
    )
    (net (code "74") (name "unconnected-(U2A-~{CTS}-Pad23)") (class "Default")
      (node (ref "U2") (pin "23") (pinfunction "~{CTS}_23") (pintype "input+no_connect"))
    )
    (net (code "75") (name "unconnected-(U2A-~{DCD}-Pad1)") (class "Default")
      (node (ref "U2") (pin "1") (pinfunction "~{DCD}_1") (pintype "input+no_connect"))
    )
    (net (code "76") (name "unconnected-(U2A-~{DSR}-Pad27)") (class "Default")
      (node (ref "U2") (pin "27") (pinfunction "~{DSR}_27") (pintype "input+no_connect"))
    )
    (net (code "77") (name "unconnected-(U2A-~{RI}-Pad2)") (class "Default")
      (node (ref "U2") (pin "2") (pinfunction "~{RI}_2") (pintype "input+no_connect"))
    )
    (net (code "78") (name "unconnected-(U2A-~{RST}-Pad9)") (class "Default")
      (node (ref "U2") (pin "9") (pinfunction "~{RST}_9") (pintype "bidirectional+no_connect"))
    )
    (net (code "79") (name "unconnected-(U2A-~{SUSPEND}-Pad11)") (class "Default")
      (node (ref "U2") (pin "11") (pinfunction "~{SUSPEND}_11") (pintype "output+no_connect"))
    )
  )
)
